# motor_driver.net
KiCad netlist of a schematic drawn in EAGLE
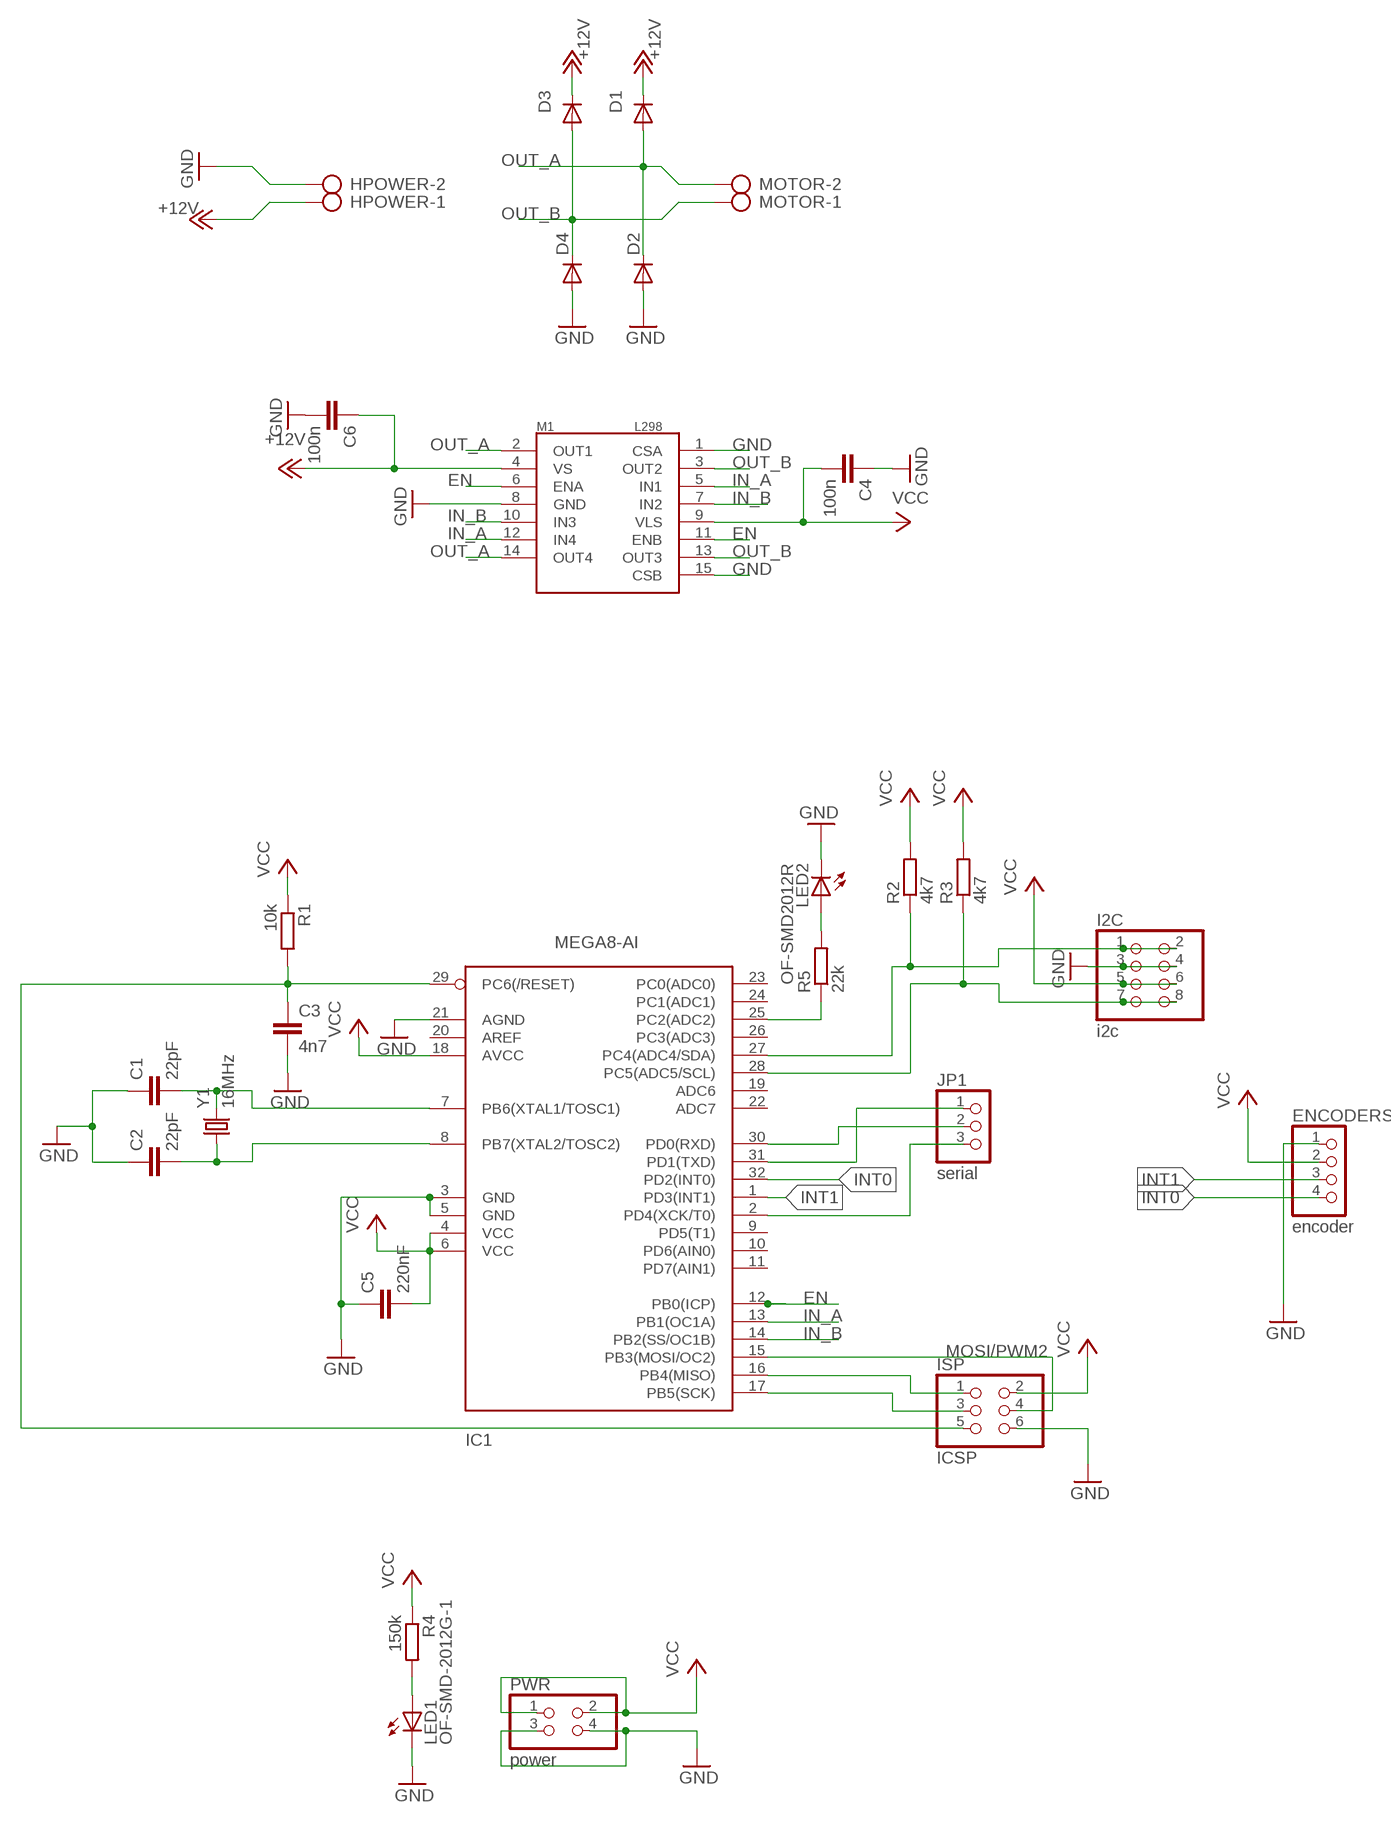
[diagram p0: schematic, sheet 1]

(export (version "E")
  (design (tool "Eeschema 10.0.6"))
  (components
    (comp (ref "C1")
      (value "22pF")
      (footprint "eagle-import:C0805")
      (libsource (lib "eagle-import") (part "C"))
    )
    (comp (ref "C2")
      (value "22pF")
      (footprint "eagle-import:C0805")
      (libsource (lib "eagle-import") (part "C"))
    )
    (comp (ref "C3")
      (value "4n7")
      (footprint "eagle-import:0805")
      (libsource (lib "eagle-import") (part "CAP0805"))
    )
    (comp (ref "C4")
      (value "100n")
      (footprint "eagle-import:0805")
      (libsource (lib "eagle-import") (part "CAP0805"))
    )
    (comp (ref "C5")
      (value "220nF")
      (footprint "eagle-import:0805")
      (libsource (lib "eagle-import") (part "CAP0805"))
    )
    (comp (ref "C6")
      (value "100n")
      (footprint "eagle-import:C0805")
      (libsource (lib "eagle-import") (part "C"))
    )
    (comp (ref "D1")
      (value "DIODE-SMB")
      (footprint "eagle-import:SMB")
      (libsource (lib "eagle-import") (part "DIODE-SMB"))
    )
    (comp (ref "D2")
      (value "DIODE-SMB")
      (footprint "eagle-import:SMB")
      (libsource (lib "eagle-import") (part "DIODE-SMB"))
    )
    (comp (ref "D3")
      (value "DIODE-SMB")
      (footprint "eagle-import:SMB")
      (libsource (lib "eagle-import") (part "DIODE-SMB"))
    )
    (comp (ref "D4")
      (value "DIODE-SMB")
      (footprint "eagle-import:SMB")
      (libsource (lib "eagle-import") (part "DIODE-SMB"))
    )
    (comp (ref "ENCODERS")
      (value "encoder")
      (footprint "eagle-import:1X04-S")
      (libsource (lib "eagle-import") (part "PINHD-1X04_2.54-S"))
    )
    (comp (ref "HPOWER")
      (value "AK500/2")
      (footprint "eagle-import:AK500_2")
      (libsource (lib "eagle-import") (part "AK500/2"))
    )
    (comp (ref "I2C")
      (value "i2c")
      (footprint "eagle-import:2X04")
      (libsource (lib "eagle-import") (part "PINHD-2X04_2.54"))
    )
    (comp (ref "IC1")
      (value "MEGA8-AI")
      (footprint "eagle-import:TQFP32-08")
      (libsource (lib "eagle-import") (part "MEGA8-AI"))
    )
    (comp (ref "ISP")
      (value "ICSP")
      (footprint "eagle-import:2X03")
      (libsource (lib "eagle-import") (part "PINHD-2X03_2.54"))
    )
    (comp (ref "JP1")
      (value "serial")
      (footprint "eagle-import:1X03-S")
      (libsource (lib "eagle-import") (part "PINHD-1X03_2.54-S"))
    )
    (comp (ref "LED1")
      (value "OF-SMD-2012G-1")
      (footprint "eagle-import:CHIPLED_1206")
      (libsource (lib "eagle-import") (part "LEDCHIPLED_1206"))
    )
    (comp (ref "LED2")
      (value "OF-SMD2012R")
      (footprint "eagle-import:CHIPLED_1206")
      (libsource (lib "eagle-import") (part "LEDCHIPLED_1206"))
    )
    (comp (ref "M1")
      (value "L298")
      (footprint "eagle-import:MULTIWATT15")
      (libsource (lib "eagle-import") (part "L298"))
    )
    (comp (ref "MOTOR")
      (value "AK500/2")
      (footprint "eagle-import:AK500_2")
      (libsource (lib "eagle-import") (part "AK500/2"))
    )
    (comp (ref "PWR")
      (value "power")
      (footprint "eagle-import:2X02")
      (libsource (lib "eagle-import") (part "PINHD-2X02_2.54"))
    )
    (comp (ref "R1")
      (value "10k")
      (footprint "eagle-import:R0805")
      (libsource (lib "eagle-import") (part "R"))
    )
    (comp (ref "R2")
      (value "4k7")
      (footprint "eagle-import:R0805")
      (libsource (lib "eagle-import") (part "R"))
    )
    (comp (ref "R3")
      (value "4k7")
      (footprint "eagle-import:R0805")
      (libsource (lib "eagle-import") (part "R"))
    )
    (comp (ref "R4")
      (value "150k")
      (footprint "eagle-import:R0805")
      (libsource (lib "eagle-import") (part "R"))
    )
    (comp (ref "R5")
      (value "22k")
      (footprint "eagle-import:R0805")
      (libsource (lib "eagle-import") (part "R"))
    )
    (comp (ref "Y1")
      (value "16MHz")
      (footprint "eagle-import:HC49UP")
      (libsource (lib "eagle-import") (part "CRYSTALSMD"))
    )
  )
  (nets
    (net (code "1") (name "+12V") (class "Default")
      (node (ref "C6") (pin "1") (pinfunction "1_1") (pintype "passive"))
      (node (ref "D1") (pin "C") (pinfunction "C_C") (pintype "passive"))
      (node (ref "D3") (pin "C") (pinfunction "C_C") (pintype "passive"))
      (node (ref "HPOWER") (pin "1") (pinfunction "KL_1") (pintype "passive"))
      (node (ref "M1") (pin "4") (pinfunction "VS_4") (pintype "bidirectional"))
    )
    (net (code "2") (name "/EN") (class "Default")
      (node (ref "IC1") (pin "12") (pinfunction "PB0(ICP)_12") (pintype "bidirectional"))
      (node (ref "M1") (pin "11") (pinfunction "ENB_11") (pintype "bidirectional"))
      (node (ref "M1") (pin "6") (pinfunction "ENA_6") (pintype "bidirectional"))
    )
    (net (code "3") (name "/IN_A") (class "Default")
      (node (ref "IC1") (pin "13") (pinfunction "PB1(OC1A)_13") (pintype "bidirectional"))
      (node (ref "M1") (pin "12") (pinfunction "IN4_12") (pintype "bidirectional"))
      (node (ref "M1") (pin "5") (pinfunction "IN1_5") (pintype "bidirectional"))
    )
    (net (code "4") (name "/IN_B") (class "Default")
      (node (ref "IC1") (pin "14") (pinfunction "PB2(SS/OC1B)_14") (pintype "bidirectional"))
      (node (ref "M1") (pin "10") (pinfunction "IN3_10") (pintype "bidirectional"))
      (node (ref "M1") (pin "7") (pinfunction "IN2_7") (pintype "bidirectional"))
    )
    (net (code "5") (name "/MOSI{slash}PWM2") (class "Default")
      (node (ref "IC1") (pin "15") (pinfunction "PB3(MOSI/OC2)_15") (pintype "bidirectional"))
      (node (ref "ISP") (pin "4") (pinfunction "4_4") (pintype "passive"))
    )
    (net (code "6") (name "/OUT_A") (class "Default")
      (node (ref "D1") (pin "A") (pinfunction "A_A") (pintype "passive"))
      (node (ref "D2") (pin "C") (pinfunction "C_C") (pintype "passive"))
      (node (ref "M1") (pin "14") (pinfunction "OUT4_14") (pintype "bidirectional"))
      (node (ref "M1") (pin "2") (pinfunction "OUT1_2") (pintype "bidirectional"))
      (node (ref "MOTOR") (pin "2") (pinfunction "KL_2") (pintype "passive"))
    )
    (net (code "7") (name "/OUT_B") (class "Default")
      (node (ref "D3") (pin "A") (pinfunction "A_A") (pintype "passive"))
      (node (ref "D4") (pin "C") (pinfunction "C_C") (pintype "passive"))
      (node (ref "M1") (pin "13") (pinfunction "OUT3_13") (pintype "bidirectional"))
      (node (ref "M1") (pin "3") (pinfunction "OUT2_3") (pintype "bidirectional"))
      (node (ref "MOTOR") (pin "1") (pinfunction "KL_1") (pintype "passive"))
    )
    (net (code "8") (name "GND") (class "Default")
      (node (ref "C1") (pin "1") (pinfunction "1_1") (pintype "passive"))
      (node (ref "C2") (pin "1") (pinfunction "1_1") (pintype "passive"))
      (node (ref "C3") (pin "2") (pinfunction "2_2") (pintype "passive"))
      (node (ref "C4") (pin "1") (pinfunction "1_1") (pintype "passive"))
      (node (ref "C5") (pin "1") (pinfunction "1_1") (pintype "passive"))
      (node (ref "C6") (pin "2") (pinfunction "2_2") (pintype "passive"))
      (node (ref "D2") (pin "A") (pinfunction "A_A") (pintype "passive"))
      (node (ref "D4") (pin "A") (pinfunction "A_A") (pintype "passive"))
      (node (ref "ENCODERS") (pin "1") (pinfunction "1_1") (pintype "passive"))
      (node (ref "HPOWER") (pin "2") (pinfunction "KL_2") (pintype "passive"))
      (node (ref "I2C") (pin "3") (pinfunction "3_3") (pintype "passive"))
      (node (ref "I2C") (pin "4") (pinfunction "4_4") (pintype "passive"))
      (node (ref "IC1") (pin "21") (pinfunction "AGND_21") (pintype "bidirectional"))
      (node (ref "IC1") (pin "3") (pinfunction "GND_3") (pintype "bidirectional"))
      (node (ref "IC1") (pin "5") (pinfunction "GND_5") (pintype "bidirectional"))
      (node (ref "ISP") (pin "6") (pinfunction "6_6") (pintype "passive"))
      (node (ref "LED1") (pin "C") (pinfunction "C_C") (pintype "passive"))
      (node (ref "LED2") (pin "C") (pinfunction "C_C") (pintype "passive"))
      (node (ref "M1") (pin "1") (pinfunction "CSA_1") (pintype "bidirectional"))
      (node (ref "M1") (pin "15") (pinfunction "CSB_15") (pintype "bidirectional"))
      (node (ref "M1") (pin "8") (pinfunction "GND_8") (pintype "bidirectional"))
      (node (ref "PWR") (pin "3") (pinfunction "3_3") (pintype "passive"))
      (node (ref "PWR") (pin "4") (pinfunction "4_4") (pintype "passive"))
    )
    (net (code "9") (name "INT0") (class "Default")
      (node (ref "ENCODERS") (pin "4") (pinfunction "4_4") (pintype "passive"))
      (node (ref "IC1") (pin "32") (pinfunction "PD2(INT0)_32") (pintype "bidirectional"))
    )
    (net (code "10") (name "INT1") (class "Default")
      (node (ref "ENCODERS") (pin "3") (pinfunction "3_3") (pintype "passive"))
      (node (ref "IC1") (pin "1") (pinfunction "PD3(INT1)_1") (pintype "bidirectional"))
    )
    (net (code "11") (name "Net-(IC1-PB4(MISO))") (class "Default")
      (node (ref "IC1") (pin "16") (pinfunction "PB4(MISO)_16") (pintype "bidirectional"))
      (node (ref "ISP") (pin "1") (pinfunction "1_1") (pintype "passive"))
    )
    (net (code "12") (name "Net-(IC1-PB5(SCK))") (class "Default")
      (node (ref "IC1") (pin "17") (pinfunction "PB5(SCK)_17") (pintype "bidirectional"))
      (node (ref "ISP") (pin "3") (pinfunction "3_3") (pintype "passive"))
    )
    (net (code "13") (name "Net-(IC1-PB6(XTAL1{slash}TOSC1))") (class "Default")
      (node (ref "C1") (pin "2") (pinfunction "2_2") (pintype "passive"))
      (node (ref "IC1") (pin "7") (pinfunction "PB6(XTAL1/TOSC1)_7") (pintype "bidirectional"))
      (node (ref "Y1") (pin "2") (pinfunction "2_2") (pintype "passive"))
    )
    (net (code "14") (name "Net-(IC1-PB7(XTAL2{slash}TOSC2))") (class "Default")
      (node (ref "C2") (pin "2") (pinfunction "2_2") (pintype "passive"))
      (node (ref "IC1") (pin "8") (pinfunction "PB7(XTAL2/TOSC2)_8") (pintype "bidirectional"))
      (node (ref "Y1") (pin "1") (pinfunction "1_1") (pintype "passive"))
    )
    (net (code "15") (name "Net-(IC1-PC2(ADC2))") (class "Default")
      (node (ref "IC1") (pin "25") (pinfunction "PC2(ADC2)_25") (pintype "bidirectional"))
      (node (ref "R5") (pin "1") (pinfunction "1_1") (pintype "passive"))
    )
    (net (code "16") (name "Net-(IC1-PC4(ADC4{slash}SDA))") (class "Default")
      (node (ref "I2C") (pin "1") (pinfunction "1_1") (pintype "passive"))
      (node (ref "I2C") (pin "2") (pinfunction "2_2") (pintype "passive"))
      (node (ref "IC1") (pin "27") (pinfunction "PC4(ADC4/SDA)_27") (pintype "bidirectional"))
      (node (ref "R2") (pin "1") (pinfunction "1_1") (pintype "passive"))
    )
    (net (code "17") (name "Net-(IC1-PC5(ADC5{slash}SCL))") (class "Default")
      (node (ref "I2C") (pin "7") (pinfunction "7_7") (pintype "passive"))
      (node (ref "I2C") (pin "8") (pinfunction "8_8") (pintype "passive"))
      (node (ref "IC1") (pin "28") (pinfunction "PC5(ADC5/SCL)_28") (pintype "bidirectional"))
      (node (ref "R3") (pin "1") (pinfunction "1_1") (pintype "passive"))
    )
    (net (code "18") (name "Net-(IC1-PC6({slash}RESET))") (class "Default")
      (node (ref "C3") (pin "1") (pinfunction "1_1") (pintype "passive"))
      (node (ref "IC1") (pin "29") (pinfunction "PC6(/RESET)_29") (pintype "bidirectional"))
      (node (ref "ISP") (pin "5") (pinfunction "5_5") (pintype "passive"))
      (node (ref "R1") (pin "2") (pinfunction "2_2") (pintype "passive"))
    )
    (net (code "19") (name "Net-(IC1-PD0(RXD))") (class "Default")
      (node (ref "IC1") (pin "30") (pinfunction "PD0(RXD)_30") (pintype "bidirectional"))
      (node (ref "JP1") (pin "2") (pinfunction "2_2") (pintype "passive"))
    )
    (net (code "20") (name "Net-(IC1-PD1(TXD))") (class "Default")
      (node (ref "IC1") (pin "31") (pinfunction "PD1(TXD)_31") (pintype "bidirectional"))
      (node (ref "JP1") (pin "1") (pinfunction "1_1") (pintype "passive"))
    )
    (net (code "21") (name "Net-(IC1-PD4(XCK{slash}T0))") (class "Default")
      (node (ref "IC1") (pin "2") (pinfunction "PD4(XCK/T0)_2") (pintype "bidirectional"))
      (node (ref "JP1") (pin "3") (pinfunction "3_3") (pintype "passive"))
    )
    (net (code "22") (name "Net-(LED1-PadA)") (class "Default")
      (node (ref "LED1") (pin "A") (pinfunction "A_A") (pintype "passive"))
      (node (ref "R4") (pin "2") (pinfunction "2_2") (pintype "passive"))
    )
    (net (code "23") (name "Net-(LED2-PadA)") (class "Default")
      (node (ref "LED2") (pin "A") (pinfunction "A_A") (pintype "passive"))
      (node (ref "R5") (pin "2") (pinfunction "2_2") (pintype "passive"))
    )
    (net (code "24") (name "VCC") (class "Default")
      (node (ref "C4") (pin "2") (pinfunction "2_2") (pintype "passive"))
      (node (ref "C5") (pin "2") (pinfunction "2_2") (pintype "passive"))
      (node (ref "ENCODERS") (pin "2") (pinfunction "2_2") (pintype "passive"))
      (node (ref "I2C") (pin "5") (pinfunction "5_5") (pintype "passive"))
      (node (ref "I2C") (pin "6") (pinfunction "6_6") (pintype "passive"))
      (node (ref "IC1") (pin "18") (pinfunction "AVCC_18") (pintype "bidirectional"))
      (node (ref "IC1") (pin "4") (pinfunction "VCC_4") (pintype "bidirectional"))
      (node (ref "IC1") (pin "6") (pinfunction "VCC_6") (pintype "bidirectional"))
      (node (ref "ISP") (pin "2") (pinfunction "2_2") (pintype "passive"))
      (node (ref "M1") (pin "9") (pinfunction "VLS_9") (pintype "bidirectional"))
      (node (ref "PWR") (pin "1") (pinfunction "1_1") (pintype "passive"))
      (node (ref "PWR") (pin "2") (pinfunction "2_2") (pintype "passive"))
      (node (ref "R1") (pin "1") (pinfunction "1_1") (pintype "passive"))
      (node (ref "R2") (pin "2") (pinfunction "2_2") (pintype "passive"))
      (node (ref "R3") (pin "2") (pinfunction "2_2") (pintype "passive"))
      (node (ref "R4") (pin "1") (pinfunction "1_1") (pintype "passive"))
    )
    (net (code "25") (name "unconnected-(IC1-ADC6-Pad19)") (class "Default")
      (node (ref "IC1") (pin "19") (pinfunction "ADC6_19") (pintype "bidirectional"))
    )
    (net (code "26") (name "unconnected-(IC1-ADC7-Pad22)") (class "Default")
      (node (ref "IC1") (pin "22") (pinfunction "ADC7_22") (pintype "bidirectional"))
    )
    (net (code "27") (name "unconnected-(IC1-AREF-Pad20)") (class "Default")
      (node (ref "IC1") (pin "20") (pinfunction "AREF_20") (pintype "bidirectional"))
    )
    (net (code "28") (name "unconnected-(IC1-PC0(ADC0)-Pad23)") (class "Default")
      (node (ref "IC1") (pin "23") (pinfunction "PC0(ADC0)_23") (pintype "bidirectional"))
    )
    (net (code "29") (name "unconnected-(IC1-PC1(ADC1)-Pad24)") (class "Default")
      (node (ref "IC1") (pin "24") (pinfunction "PC1(ADC1)_24") (pintype "bidirectional"))
    )
    (net (code "30") (name "unconnected-(IC1-PC3(ADC3)-Pad26)") (class "Default")
      (node (ref "IC1") (pin "26") (pinfunction "PC3(ADC3)_26") (pintype "bidirectional"))
    )
    (net (code "31") (name "unconnected-(IC1-PD5(T1)-Pad9)") (class "Default")
      (node (ref "IC1") (pin "9") (pinfunction "PD5(T1)_9") (pintype "bidirectional"))
    )
    (net (code "32") (name "unconnected-(IC1-PD6(AIN0)-Pad10)") (class "Default")
      (node (ref "IC1") (pin "10") (pinfunction "PD6(AIN0)_10") (pintype "bidirectional"))
    )
    (net (code "33") (name "unconnected-(IC1-PD7(AIN1)-Pad11)") (class "Default")
      (node (ref "IC1") (pin "11") (pinfunction "PD7(AIN1)_11") (pintype "bidirectional"))
    )
  )
)
